# Uno.net
KiCad netlist of a schematic drawn in EAGLE
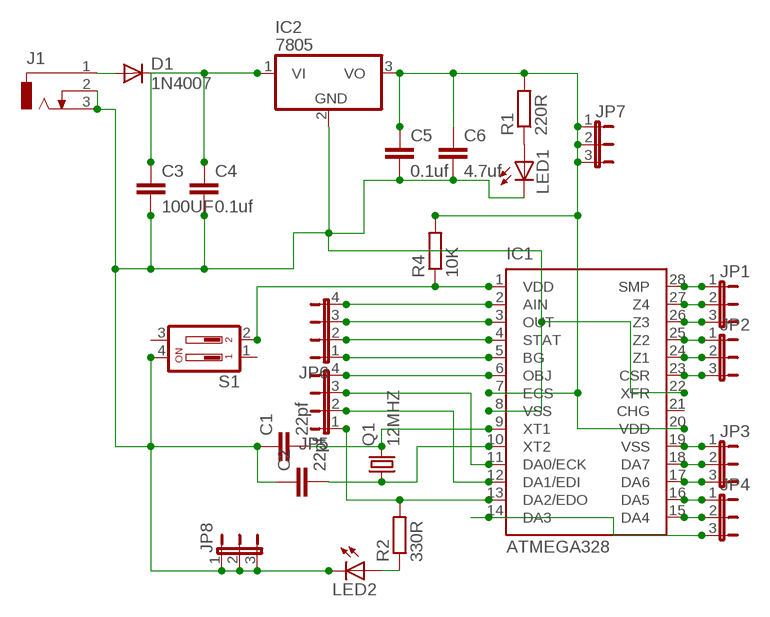
[diagram p0: schematic, sheet 1]

(export (version "E")
  (design (tool "Eeschema 10.0.6"))
  (components
    (comp (ref "C1")
      (value "22pf")
      (footprint "eagle-import:C2.5-2")
      (libsource (lib "eagle-import") (part "C2.5/2"))
    )
    (comp (ref "C2")
      (value "22pf")
      (footprint "eagle-import:C2.5-2")
      (libsource (lib "eagle-import") (part "C2.5/2"))
    )
    (comp (ref "C3")
      (value "100UF")
      (footprint "eagle-import:C2.5-2")
      (libsource (lib "eagle-import") (part "C2.5/2"))
    )
    (comp (ref "C4")
      (value "0.1uf")
      (footprint "eagle-import:C2.5-2")
      (libsource (lib "eagle-import") (part "C2.5/2"))
    )
    (comp (ref "C5")
      (value "0.1uf")
      (footprint "eagle-import:C2.5-2")
      (libsource (lib "eagle-import") (part "C2.5/2"))
    )
    (comp (ref "C6")
      (value "4.7uf")
      (footprint "eagle-import:C2.5-2")
      (libsource (lib "eagle-import") (part "C2.5/2"))
    )
    (comp (ref "D1")
      (value "1N4007")
      (footprint "eagle-import:DO41-10")
      (libsource (lib "eagle-import") (part "1N4004"))
    )
    (comp (ref "IC1")
      (value "ATMEGA328")
      (footprint "eagle-import:DIL28-3")
      (libsource (lib "eagle-import") (part "QT9701BD"))
    )
    (comp (ref "IC2")
      (value "7805")
      (footprint "eagle-import:TO220V")
      (libsource (lib "eagle-import") (part "78TV6"))
    )
    (comp (ref "J1")
      (value "DCJ0303")
      (footprint "eagle-import:DCJ0303")
      (libsource (lib "eagle-import") (part "DCJ0303"))
    )
    (comp (ref "JP1")
      (value "JP2E")
      (footprint "eagle-import:JP2")
      (libsource (lib "eagle-import") (part "JP2E"))
    )
    (comp (ref "JP2")
      (value "JP2E")
      (footprint "eagle-import:JP2")
      (libsource (lib "eagle-import") (part "JP2E"))
    )
    (comp (ref "JP3")
      (value "JP2E")
      (footprint "eagle-import:JP2")
      (libsource (lib "eagle-import") (part "JP2E"))
    )
    (comp (ref "JP4")
      (value "JP2E")
      (footprint "eagle-import:JP2")
      (libsource (lib "eagle-import") (part "JP2E"))
    )
    (comp (ref "JP5")
      (value "JP4E")
      (footprint "eagle-import:JP4")
      (libsource (lib "eagle-import") (part "JP4E"))
    )
    (comp (ref "JP6")
      (value "JP4E")
      (footprint "eagle-import:JP4")
      (libsource (lib "eagle-import") (part "JP4E"))
    )
    (comp (ref "JP7")
      (value "JP2E")
      (footprint "eagle-import:JP2")
      (libsource (lib "eagle-import") (part "JP2E"))
    )
    (comp (ref "JP8")
      (value "JP2E")
      (footprint "eagle-import:JP2")
      (libsource (lib "eagle-import") (part "JP2E"))
    )
    (comp (ref "LED1")
      (value "LED3MM")
      (footprint "eagle-import:LED3MM")
      (libsource (lib "eagle-import") (part "LED3MM"))
    )
    (comp (ref "LED2")
      (value "LED3MM")
      (footprint "eagle-import:LED3MM")
      (libsource (lib "eagle-import") (part "LED3MM"))
    )
    (comp (ref "Q1")
      (value "12MHZ")
      (footprint "eagle-import:HC49_S")
      (libsource (lib "eagle-import") (part "CRYSTALHC49S"))
    )
    (comp (ref "R1")
      (value "220R")
      (footprint "eagle-import:0207_10")
      (libsource (lib "eagle-import") (part "R-EU_0207/10"))
    )
    (comp (ref "R2")
      (value "330R")
      (footprint "eagle-import:0207_10")
      (libsource (lib "eagle-import") (part "R-EU_0207/10"))
    )
    (comp (ref "R4")
      (value "10K")
      (footprint "eagle-import:0207_10")
      (libsource (lib "eagle-import") (part "R-EU_0207/10"))
    )
    (comp (ref "S1")
      (value "DP02")
      (footprint "eagle-import:DP-02")
      (fields (field (name "MPN") "MCDP02"))
      (libsource (lib "eagle-import") (part "DP02"))
    )
  )
  (nets
    (net (code "1") (name "Net-(D1-PadA)") (class "Default")
      (node (ref "D1") (pin "A") (pinfunction "A_A") (pintype "passive"))
      (node (ref "J1") (pin "1") (pinfunction "1_1") (pintype "passive"))
    )
    (net (code "2") (name "Net-(IC1-AIN)") (class "Default")
      (node (ref "IC1") (pin "2") (pinfunction "AIN_2") (pintype "input"))
      (node (ref "JP6") (pin "4") (pinfunction "4_4") (pintype "passive"))
    )
    (net (code "3") (name "Net-(IC1-BG)") (class "Default")
      (node (ref "IC1") (pin "5") (pinfunction "BG_5") (pintype "input"))
      (node (ref "JP6") (pin "1") (pinfunction "1_1") (pintype "passive"))
    )
    (net (code "4") (name "Net-(IC1-CSR)") (class "Default")
      (node (ref "IC1") (pin "23") (pinfunction "CSR_23") (pintype "output"))
      (node (ref "JP2") (pin "3") (pinfunction "3_3") (pintype "passive"))
    )
    (net (code "5") (name "Net-(IC1-DA0{slash}ECK)") (class "Default")
      (node (ref "IC1") (pin "11") (pinfunction "DA0/ECK_11") (pintype "output"))
      (node (ref "JP5") (pin "3") (pinfunction "3_3") (pintype "passive"))
    )
    (net (code "6") (name "Net-(IC1-DA1{slash}EDI)") (class "Default")
      (node (ref "IC1") (pin "12") (pinfunction "DA1/EDI_12") (pintype "output"))
      (node (ref "JP5") (pin "2") (pinfunction "2_2") (pintype "passive"))
    )
    (net (code "7") (name "Net-(IC1-DA2{slash}EDO)") (class "Default")
      (node (ref "IC1") (pin "13") (pinfunction "DA2/EDO_13") (pintype "output"))
      (node (ref "JP5") (pin "1") (pinfunction "1_1") (pintype "passive"))
      (node (ref "R2") (pin "2") (pinfunction "2_2") (pintype "passive"))
    )
    (net (code "8") (name "Net-(IC1-DA3)") (class "Default")
      (node (ref "IC1") (pin "14") (pinfunction "DA3_14") (pintype "output"))
      (node (ref "JP4") (pin "3") (pinfunction "3_3") (pintype "passive"))
    )
    (net (code "9") (name "Net-(IC1-DA4)") (class "Default")
      (node (ref "IC1") (pin "15") (pinfunction "DA4_15") (pintype "output"))
      (node (ref "JP4") (pin "2") (pinfunction "2_2") (pintype "passive"))
    )
    (net (code "10") (name "Net-(IC1-DA5)") (class "Default")
      (node (ref "IC1") (pin "16") (pinfunction "DA5_16") (pintype "output"))
      (node (ref "JP4") (pin "1") (pinfunction "1_1") (pintype "passive"))
    )
    (net (code "11") (name "Net-(IC1-DA6)") (class "Default")
      (node (ref "IC1") (pin "17") (pinfunction "DA6_17") (pintype "output"))
      (node (ref "JP3") (pin "3") (pinfunction "3_3") (pintype "passive"))
    )
    (net (code "12") (name "Net-(IC1-DA7)") (class "Default")
      (node (ref "IC1") (pin "18") (pinfunction "DA7_18") (pintype "output"))
      (node (ref "JP3") (pin "2") (pinfunction "2_2") (pintype "passive"))
    )
    (net (code "13") (name "Net-(IC1-ECS)") (class "Default")
      (node (ref "C5") (pin "1") (pinfunction "1_1") (pintype "passive"))
      (node (ref "C6") (pin "1") (pinfunction "1_1") (pintype "passive"))
      (node (ref "IC1") (pin "20") (pinfunction "VDD_20") (pintype "input"))
      (node (ref "IC1") (pin "7") (pinfunction "ECS_7") (pintype "output"))
      (node (ref "IC2") (pin "3") (pinfunction "VO_3") (pintype "passive"))
      (node (ref "JP7") (pin "1") (pinfunction "1_1") (pintype "passive"))
      (node (ref "JP7") (pin "2") (pinfunction "2_2") (pintype "passive"))
      (node (ref "JP7") (pin "3") (pinfunction "3_3") (pintype "passive"))
      (node (ref "R1") (pin "2") (pinfunction "2_2") (pintype "passive"))
      (node (ref "R4") (pin "2") (pinfunction "2_2") (pintype "passive"))
    )
    (net (code "14") (name "Net-(IC1-OBJ)") (class "Default")
      (node (ref "IC1") (pin "6") (pinfunction "OBJ_6") (pintype "input"))
      (node (ref "JP5") (pin "4") (pinfunction "4_4") (pintype "passive"))
    )
    (net (code "15") (name "Net-(IC1-OUT)") (class "Default")
      (node (ref "IC1") (pin "3") (pinfunction "OUT_3") (pintype "output"))
      (node (ref "JP6") (pin "3") (pinfunction "3_3") (pintype "passive"))
    )
    (net (code "16") (name "Net-(IC1-SMP)") (class "Default")
      (node (ref "IC1") (pin "28") (pinfunction "SMP_28") (pintype "output"))
      (node (ref "JP1") (pin "1") (pinfunction "1_1") (pintype "passive"))
    )
    (net (code "17") (name "Net-(IC1-STAT)") (class "Default")
      (node (ref "IC1") (pin "4") (pinfunction "STAT_4") (pintype "output"))
      (node (ref "JP6") (pin "2") (pinfunction "2_2") (pintype "passive"))
    )
    (net (code "18") (name "Net-(IC1-VDD-Pad1)") (class "Default")
      (node (ref "IC1") (pin "1") (pinfunction "VDD_1") (pintype "input"))
      (node (ref "R4") (pin "1") (pinfunction "1_1") (pintype "passive"))
      (node (ref "S1") (pin "2") (pinfunction "2_2") (pintype "passive"))
    )
    (net (code "19") (name "Net-(IC1-VSS-Pad19)") (class "Default")
      (node (ref "IC1") (pin "19") (pinfunction "VSS_19") (pintype "input"))
      (node (ref "JP3") (pin "1") (pinfunction "1_1") (pintype "passive"))
    )
    (net (code "20") (name "Net-(IC1-XFR)") (class "Default")
      (node (ref "C1") (pin "1") (pinfunction "1_1") (pintype "passive"))
      (node (ref "C2") (pin "1") (pinfunction "1_1") (pintype "passive"))
      (node (ref "C3") (pin "2") (pinfunction "2_2") (pintype "passive"))
      (node (ref "C4") (pin "2") (pinfunction "2_2") (pintype "passive"))
      (node (ref "C5") (pin "2") (pinfunction "2_2") (pintype "passive"))
      (node (ref "C6") (pin "2") (pinfunction "2_2") (pintype "passive"))
      (node (ref "IC1") (pin "22") (pinfunction "XFR_22") (pintype "output"))
      (node (ref "IC1") (pin "8") (pinfunction "VSS_8") (pintype "input"))
      (node (ref "IC2") (pin "2") (pinfunction "GND_2") (pintype "passive"))
      (node (ref "J1") (pin "2") (pinfunction "2_2") (pintype "passive"))
      (node (ref "J1") (pin "3") (pinfunction "3_3") (pintype "passive"))
      (node (ref "JP8") (pin "1") (pinfunction "1_1") (pintype "passive"))
      (node (ref "JP8") (pin "2") (pinfunction "2_2") (pintype "passive"))
      (node (ref "JP8") (pin "3") (pinfunction "3_3") (pintype "passive"))
      (node (ref "LED1") (pin "K") (pinfunction "C_K") (pintype "passive"))
      (node (ref "LED2") (pin "K") (pinfunction "C_K") (pintype "passive"))
      (node (ref "S1") (pin "4") (pinfunction "4_4") (pintype "passive"))
    )
    (net (code "21") (name "Net-(IC1-XT1)") (class "Default")
      (node (ref "C1") (pin "2") (pinfunction "2_2") (pintype "passive"))
      (node (ref "IC1") (pin "9") (pinfunction "XT1_9") (pintype "input"))
      (node (ref "Q1") (pin "2") (pinfunction "2_2") (pintype "passive"))
    )
    (net (code "22") (name "Net-(IC1-XT2)") (class "Default")
      (node (ref "C2") (pin "2") (pinfunction "2_2") (pintype "passive"))
      (node (ref "IC1") (pin "10") (pinfunction "XT2_10") (pintype "output"))
      (node (ref "Q1") (pin "1") (pinfunction "1_1") (pintype "passive"))
    )
    (net (code "23") (name "Net-(IC1-Z1)") (class "Default")
      (node (ref "IC1") (pin "24") (pinfunction "Z1_24") (pintype "output"))
      (node (ref "JP2") (pin "2") (pinfunction "2_2") (pintype "passive"))
    )
    (net (code "24") (name "Net-(IC1-Z2)") (class "Default")
      (node (ref "IC1") (pin "25") (pinfunction "Z2_25") (pintype "output"))
      (node (ref "JP2") (pin "1") (pinfunction "1_1") (pintype "passive"))
    )
    (net (code "25") (name "Net-(IC1-Z3)") (class "Default")
      (node (ref "IC1") (pin "26") (pinfunction "Z3_26") (pintype "output"))
      (node (ref "JP1") (pin "3") (pinfunction "3_3") (pintype "passive"))
    )
    (net (code "26") (name "Net-(IC1-Z4)") (class "Default")
      (node (ref "IC1") (pin "27") (pinfunction "Z4_27") (pintype "output"))
      (node (ref "JP1") (pin "2") (pinfunction "2_2") (pintype "passive"))
    )
    (net (code "27") (name "Net-(IC2-VI)") (class "Default")
      (node (ref "C3") (pin "1") (pinfunction "1_1") (pintype "passive"))
      (node (ref "C4") (pin "1") (pinfunction "1_1") (pintype "passive"))
      (node (ref "D1") (pin "C") (pinfunction "C_C") (pintype "passive"))
      (node (ref "IC2") (pin "1") (pinfunction "VI_1") (pintype "input"))
    )
    (net (code "28") (name "Net-(LED1-PadA)") (class "Default")
      (node (ref "LED1") (pin "A") (pinfunction "A_A") (pintype "passive"))
      (node (ref "R1") (pin "1") (pinfunction "1_1") (pintype "passive"))
    )
    (net (code "29") (name "Net-(LED2-PadA)") (class "Default")
      (node (ref "LED2") (pin "A") (pinfunction "A_A") (pintype "passive"))
      (node (ref "R2") (pin "1") (pinfunction "1_1") (pintype "passive"))
    )
    (net (code "30") (name "unconnected-(IC1-CHG-Pad21)") (class "Default")
      (node (ref "IC1") (pin "21") (pinfunction "CHG_21") (pintype "output"))
    )
    (net (code "31") (name "unconnected-(S1-Pad1)") (class "Default")
      (node (ref "S1") (pin "1") (pinfunction "1_1") (pintype "passive"))
    )
    (net (code "32") (name "unconnected-(S1-Pad3)") (class "Default")
      (node (ref "S1") (pin "3") (pinfunction "3_3") (pintype "passive"))
    )
  )
)
